# connector_schematic.net
KiCad netlist of a schematic drawn in EAGLE
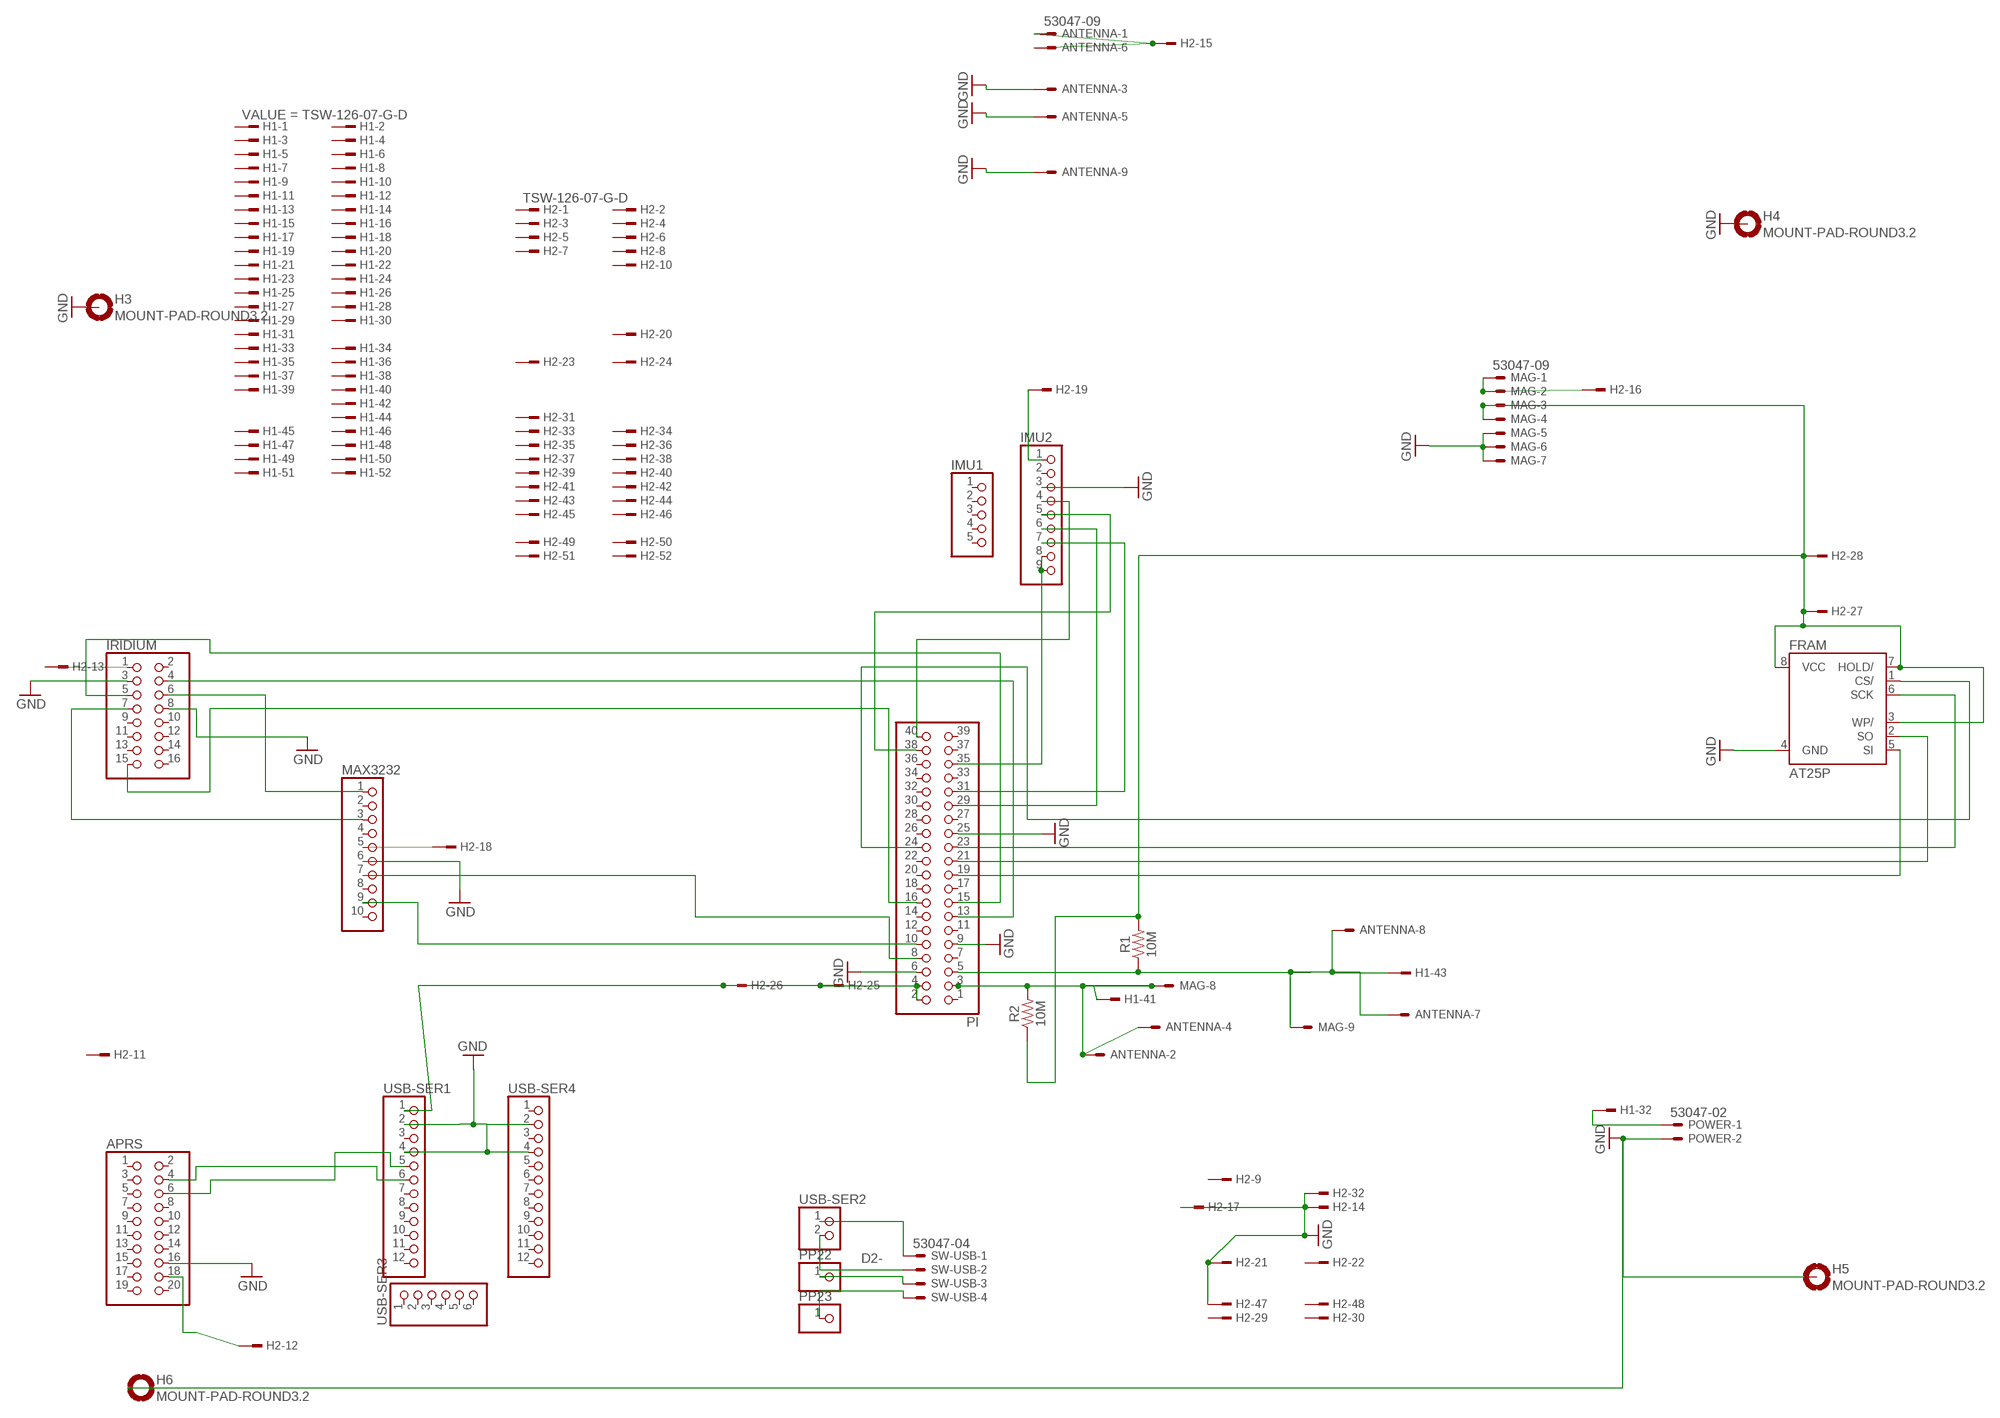
[diagram p0: schematic, sheet 1]

(export (version "E")
  (design (tool "Eeschema 10.0.6"))
  (components
    (comp (ref "ANTENNA")
      (value "53047-09")
      (footprint "eagle-import:53047-09")
      (fields (field (name "MF") "MOLEX") (field (name "MPN") "53047-0910"))
      (libsource (lib "eagle-import") (part "53?-09047"))
    )
    (comp (ref "APRS")
      (value "PINHD-2X10")
      (footprint "eagle-import:2X10")
      (libsource (lib "eagle-import") (part "PINHD-2X10"))
    )
    (comp (ref "FRAM")
      (value "AT25P")
      (footprint "eagle-import:DIL08")
      (fields (field (name "MPN") "CAT25040LI-G"))
      (libsource (lib "eagle-import") (part "AT25P"))
    )
    (comp (ref "H1")
      (value "TSW-126-07-G-D")
      (footprint "eagle-import:TSW-126-XX-G-D")
      (fields (field (name "MF") "Samtec Inc."))
      (libsource (lib "eagle-import") (part "TSW-126--G-D07"))
    )
    (comp (ref "H2")
      (value "TSW-126-07-G-D")
      (footprint "eagle-import:TSW-126-XX-G-D")
      (fields (field (name "MF") "Samtec Inc."))
      (libsource (lib "eagle-import") (part "TSW-126--G-D07"))
    )
    (comp (ref "H3")
      (value "MOUNT-PAD-ROUND3.2")
      (footprint "eagle-import:3,2-PAD")
      (libsource (lib "eagle-import") (part "MOUNT-PAD-ROUND3.2"))
    )
    (comp (ref "H4")
      (value "MOUNT-PAD-ROUND3.2")
      (footprint "eagle-import:3,2-PAD")
      (libsource (lib "eagle-import") (part "MOUNT-PAD-ROUND3.2"))
    )
    (comp (ref "H5")
      (value "MOUNT-PAD-ROUND3.2")
      (footprint "eagle-import:3,2-PAD")
      (libsource (lib "eagle-import") (part "MOUNT-PAD-ROUND3.2"))
    )
    (comp (ref "H6")
      (value "MOUNT-PAD-ROUND3.2")
      (footprint "eagle-import:3,2-PAD")
      (libsource (lib "eagle-import") (part "MOUNT-PAD-ROUND3.2"))
    )
    (comp (ref "IMU1")
      (value "PINHD-1X5")
      (footprint "eagle-import:1X05")
      (libsource (lib "eagle-import") (part "PINHD-1X5"))
    )
    (comp (ref "IMU2")
      (value "PINHD-1X9")
      (footprint "eagle-import:1X09")
      (libsource (lib "eagle-import") (part "PINHD-1X9"))
    )
    (comp (ref "IRIDIUM")
      (value "PINHD-2X8")
      (footprint "eagle-import:2X08")
      (libsource (lib "eagle-import") (part "PINHD-2X8"))
    )
    (comp (ref "MAG")
      (value "53047-09")
      (footprint "eagle-import:53047-09")
      (fields (field (name "MF") "MOLEX") (field (name "MPN") "53047-0910"))
      (libsource (lib "eagle-import") (part "53?-09047"))
    )
    (comp (ref "MAX3232")
      (value "PINHD-1X10")
      (footprint "eagle-import:1X10")
      (libsource (lib "eagle-import") (part "PINHD-1X10"))
    )
    (comp (ref "PI")
      (value "PINHD-2X20")
      (footprint "eagle-import:2X20")
      (libsource (lib "eagle-import") (part "PINHD-2X20"))
    )
    (comp (ref "POWER")
      (value "53047-02")
      (footprint "eagle-import:53047-02")
      (fields (field (name "MF") "MOLEX") (field (name "MPN") "53047-0210"))
      (libsource (lib "eagle-import") (part "53?-02047"))
    )
    (comp (ref "PP22")
      (value "PINHD-1X1")
      (footprint "eagle-import:1X01")
      (libsource (lib "eagle-import") (part "PINHD-1X1"))
    )
    (comp (ref "PP23")
      (value "PINHD-1X1")
      (footprint "eagle-import:1X01")
      (libsource (lib "eagle-import") (part "PINHD-1X1"))
    )
    (comp (ref "R1")
      (value "10M")
      (footprint "eagle-import:AXIAL-0.3")
      (libsource (lib "eagle-import") (part "10MOHM-HORIZ-1/4W-5%"))
    )
    (comp (ref "R2")
      (value "10M")
      (footprint "eagle-import:AXIAL-0.3")
      (libsource (lib "eagle-import") (part "10MOHM-HORIZ-1/4W-5%"))
    )
    (comp (ref "SW-USB")
      (value "53047-04")
      (footprint "eagle-import:53047-04")
      (fields (field (name "MF") "WALDOM/MOLEX") (field (name "MPN") "53047-0410"))
      (libsource (lib "eagle-import") (part "53?-04047"))
    )
    (comp (ref "USB-SER1")
      (value "PINHD-1X12")
      (footprint "eagle-import:1X12")
      (libsource (lib "eagle-import") (part "PINHD-1X12"))
    )
    (comp (ref "USB-SER2")
      (value "PINHD-1X2")
      (footprint "eagle-import:1X02")
      (libsource (lib "eagle-import") (part "PINHD-1X2"))
    )
    (comp (ref "USB-SER3")
      (value "PINHD-1X6")
      (footprint "eagle-import:1X06")
      (libsource (lib "eagle-import") (part "PINHD-1X6"))
    )
    (comp (ref "USB-SER4")
      (value "PINHD-1X12")
      (footprint "eagle-import:1X12")
      (libsource (lib "eagle-import") (part "PINHD-1X12"))
    )
  )
  (nets
    (net (code "1") (name "/D2-") (class "Default")
      (node (ref "SW-USB") (pin "2") (pinfunction "S_2") (pintype "passive"))
      (node (ref "USB-SER2") (pin "2") (pinfunction "2_2") (pintype "passive"))
    )
    (net (code "2") (name "GND") (class "Default")
      (node (ref "ANTENNA") (pin "3") (pinfunction "S_3") (pintype "passive"))
      (node (ref "ANTENNA") (pin "5") (pinfunction "S_5") (pintype "passive"))
      (node (ref "ANTENNA") (pin "9") (pinfunction "S_9") (pintype "passive"))
      (node (ref "APRS") (pin "16") (pinfunction "16_16") (pintype "passive"))
      (node (ref "FRAM") (pin "4") (pinfunction "GND_4") (pintype "power_in"))
      (node (ref "H2") (pin "14") (pinfunction "1_14") (pintype "passive"))
      (node (ref "H2") (pin "17") (pinfunction "1_17") (pintype "passive"))
      (node (ref "H2") (pin "21") (pinfunction "1_21") (pintype "passive"))
      (node (ref "H2") (pin "32") (pinfunction "1_32") (pintype "passive"))
      (node (ref "H2") (pin "47") (pinfunction "1_47") (pintype "passive"))
      (node (ref "H3") (pin "B3,2") (pinfunction "MOUNT_B3,2") (pintype "passive"))
      (node (ref "H4") (pin "B3,2") (pinfunction "MOUNT_B3,2") (pintype "passive"))
      (node (ref "H5") (pin "B3,2") (pinfunction "MOUNT_B3,2") (pintype "passive"))
      (node (ref "H6") (pin "B3,2") (pinfunction "MOUNT_B3,2") (pintype "passive"))
      (node (ref "IMU2") (pin "3") (pinfunction "3_3") (pintype "passive"))
      (node (ref "IRIDIUM") (pin "3") (pinfunction "3_3") (pintype "passive"))
      (node (ref "IRIDIUM") (pin "8") (pinfunction "8_8") (pintype "passive"))
      (node (ref "MAG") (pin "5") (pinfunction "S_5") (pintype "passive"))
      (node (ref "MAG") (pin "6") (pinfunction "S_6") (pintype "passive"))
      (node (ref "MAG") (pin "7") (pinfunction "S_7") (pintype "passive"))
      (node (ref "MAX3232") (pin "6") (pinfunction "6_6") (pintype "passive"))
      (node (ref "PI") (pin "25") (pinfunction "25_25") (pintype "passive"))
      (node (ref "PI") (pin "6") (pinfunction "6_6") (pintype "passive"))
      (node (ref "PI") (pin "9") (pinfunction "9_9") (pintype "passive"))
      (node (ref "POWER") (pin "2") (pinfunction "S_2") (pintype "passive"))
      (node (ref "USB-SER1") (pin "2") (pinfunction "2_2") (pintype "passive"))
      (node (ref "USB-SER1") (pin "4") (pinfunction "4_4") (pintype "passive"))
      (node (ref "USB-SER4") (pin "2") (pinfunction "2_2") (pintype "passive"))
      (node (ref "USB-SER4") (pin "4") (pinfunction "4_4") (pintype "passive"))
    )
    (net (code "3") (name "Net-(ANTENNAA-S)") (class "Default")
      (node (ref "ANTENNA") (pin "1") (pinfunction "S_1") (pintype "passive"))
      (node (ref "ANTENNA") (pin "6") (pinfunction "S_6") (pintype "passive"))
      (node (ref "H2") (pin "15") (pinfunction "1_15") (pintype "passive"))
    )
    (net (code "4") (name "Net-(ANTENNAB-S)") (class "Default")
      (node (ref "ANTENNA") (pin "2") (pinfunction "S_2") (pintype "passive"))
      (node (ref "ANTENNA") (pin "4") (pinfunction "S_4") (pintype "passive"))
      (node (ref "H1") (pin "41") (pinfunction "1_41") (pintype "passive"))
      (node (ref "MAG") (pin "8") (pinfunction "S_8") (pintype "passive"))
      (node (ref "PI") (pin "3") (pinfunction "3_3") (pintype "passive"))
      (node (ref "R2") (pin "P$2") (pinfunction "2_P$2") (pintype "passive"))
    )
    (net (code "5") (name "Net-(ANTENNAG-S)") (class "Default")
      (node (ref "ANTENNA") (pin "7") (pinfunction "S_7") (pintype "passive"))
      (node (ref "ANTENNA") (pin "8") (pinfunction "S_8") (pintype "passive"))
      (node (ref "H1") (pin "43") (pinfunction "1_43") (pintype "passive"))
      (node (ref "MAG") (pin "9") (pinfunction "S_9") (pintype "passive"))
      (node (ref "PI") (pin "5") (pinfunction "5_5") (pintype "passive"))
      (node (ref "R1") (pin "P$1") (pinfunction "1_P$1") (pintype "passive"))
    )
    (net (code "6") (name "Net-(APRS-Pad4)") (class "Default")
      (node (ref "APRS") (pin "4") (pinfunction "4_4") (pintype "passive"))
      (node (ref "USB-SER1") (pin "6") (pinfunction "6_6") (pintype "passive"))
    )
    (net (code "7") (name "Net-(APRS-Pad6)") (class "Default")
      (node (ref "APRS") (pin "6") (pinfunction "6_6") (pintype "passive"))
      (node (ref "USB-SER1") (pin "5") (pinfunction "5_5") (pintype "passive"))
    )
    (net (code "8") (name "Net-(FRAM-CS{slash})") (class "Default")
      (node (ref "FRAM") (pin "1") (pinfunction "CS/_1") (pintype "input"))
      (node (ref "PI") (pin "24") (pinfunction "24_24") (pintype "passive"))
    )
    (net (code "9") (name "Net-(FRAM-HOLD{slash})") (class "Default")
      (node (ref "FRAM") (pin "3") (pinfunction "WP/_3") (pintype "input"))
      (node (ref "FRAM") (pin "7") (pinfunction "HOLD/_7") (pintype "input"))
      (node (ref "FRAM") (pin "8") (pinfunction "VCC_8") (pintype "power_in"))
      (node (ref "H2") (pin "27") (pinfunction "1_27") (pintype "passive"))
      (node (ref "H2") (pin "28") (pinfunction "1_28") (pintype "passive"))
      (node (ref "MAG") (pin "3") (pinfunction "S_3") (pintype "passive"))
      (node (ref "MAG") (pin "4") (pinfunction "S_4") (pintype "passive"))
      (node (ref "R1") (pin "P$2") (pinfunction "2_P$2") (pintype "passive"))
      (node (ref "R2") (pin "P$1") (pinfunction "1_P$1") (pintype "passive"))
    )
    (net (code "10") (name "Net-(FRAM-SCK)") (class "Default")
      (node (ref "FRAM") (pin "6") (pinfunction "SCK_6") (pintype "bidirectional"))
      (node (ref "PI") (pin "23") (pinfunction "23_23") (pintype "passive"))
    )
    (net (code "11") (name "Net-(FRAM-SI)") (class "Default")
      (node (ref "FRAM") (pin "5") (pinfunction "SI_5") (pintype "bidirectional"))
      (node (ref "PI") (pin "19") (pinfunction "19_19") (pintype "passive"))
    )
    (net (code "12") (name "Net-(FRAM-SO)") (class "Default")
      (node (ref "FRAM") (pin "2") (pinfunction "SO_2") (pintype "input"))
      (node (ref "PI") (pin "21") (pinfunction "21_21") (pintype "passive"))
    )
    (net (code "13") (name "Net-(H1Z-1)") (class "Default")
      (node (ref "H1") (pin "32") (pinfunction "1_32") (pintype "passive"))
      (node (ref "POWER") (pin "1") (pinfunction "S_1") (pintype "passive"))
    )
    (net (code "14") (name "Net-(H2D-1)") (class "Default")
      (node (ref "APRS") (pin "18") (pinfunction "18_18") (pintype "passive"))
      (node (ref "H2") (pin "12") (pinfunction "1_12") (pintype "passive"))
    )
    (net (code "15") (name "Net-(H2E-1)") (class "Default")
      (node (ref "H2") (pin "13") (pinfunction "1_13") (pintype "passive"))
      (node (ref "IRIDIUM") (pin "1") (pinfunction "1_1") (pintype "passive"))
    )
    (net (code "16") (name "Net-(H2H-1)") (class "Default")
      (node (ref "H2") (pin "16") (pinfunction "1_16") (pintype "passive"))
      (node (ref "MAG") (pin "1") (pinfunction "S_1") (pintype "passive"))
      (node (ref "MAG") (pin "2") (pinfunction "S_2") (pintype "passive"))
    )
    (net (code "17") (name "Net-(H2J-1)") (class "Default")
      (node (ref "H2") (pin "18") (pinfunction "1_18") (pintype "passive"))
      (node (ref "MAX3232") (pin "5") (pinfunction "5_5") (pintype "passive"))
    )
    (net (code "18") (name "Net-(H2K-1)") (class "Default")
      (node (ref "H2") (pin "19") (pinfunction "1_19") (pintype "passive"))
      (node (ref "IMU2") (pin "1") (pinfunction "1_1") (pintype "passive"))
    )
    (net (code "19") (name "Net-(H2R-1)") (class "Default")
      (node (ref "H2") (pin "25") (pinfunction "1_25") (pintype "passive"))
      (node (ref "H2") (pin "26") (pinfunction "1_26") (pintype "passive"))
      (node (ref "PI") (pin "2") (pinfunction "2_2") (pintype "passive"))
      (node (ref "PI") (pin "4") (pinfunction "4_4") (pintype "passive"))
      (node (ref "USB-SER1") (pin "1") (pinfunction "1_1") (pintype "passive"))
    )
    (net (code "20") (name "Net-(IMU2-Pad4)") (class "Default")
      (node (ref "IMU2") (pin "4") (pinfunction "4_4") (pintype "passive"))
      (node (ref "PI") (pin "40") (pinfunction "40_40") (pintype "passive"))
    )
    (net (code "21") (name "Net-(IMU2-Pad5)") (class "Default")
      (node (ref "IMU2") (pin "5") (pinfunction "5_5") (pintype "passive"))
      (node (ref "PI") (pin "38") (pinfunction "38_38") (pintype "passive"))
    )
    (net (code "22") (name "Net-(IMU2-Pad6)") (class "Default")
      (node (ref "IMU2") (pin "6") (pinfunction "6_6") (pintype "passive"))
      (node (ref "PI") (pin "29") (pinfunction "29_29") (pintype "passive"))
    )
    (net (code "23") (name "Net-(IMU2-Pad7)") (class "Default")
      (node (ref "IMU2") (pin "7") (pinfunction "7_7") (pintype "passive"))
      (node (ref "PI") (pin "31") (pinfunction "31_31") (pintype "passive"))
    )
    (net (code "24") (name "Net-(IMU2-Pad8)") (class "Default")
      (node (ref "IMU2") (pin "8") (pinfunction "8_8") (pintype "passive"))
      (node (ref "IMU2") (pin "9") (pinfunction "9_9") (pintype "passive"))
      (node (ref "PI") (pin "35") (pinfunction "35_35") (pintype "passive"))
    )
    (net (code "25") (name "Net-(IRIDIUM-Pad4)") (class "Default")
      (node (ref "IRIDIUM") (pin "4") (pinfunction "4_4") (pintype "passive"))
      (node (ref "PI") (pin "13") (pinfunction "13_13") (pintype "passive"))
    )
    (net (code "26") (name "Net-(IRIDIUM-Pad5)") (class "Default")
      (node (ref "IRIDIUM") (pin "5") (pinfunction "5_5") (pintype "passive"))
      (node (ref "PI") (pin "15") (pinfunction "15_15") (pintype "passive"))
    )
    (net (code "27") (name "Net-(IRIDIUM-Pad6)") (class "Default")
      (node (ref "IRIDIUM") (pin "6") (pinfunction "6_6") (pintype "passive"))
      (node (ref "MAX3232") (pin "1") (pinfunction "1_1") (pintype "passive"))
    )
    (net (code "28") (name "Net-(IRIDIUM-Pad7)") (class "Default")
      (node (ref "IRIDIUM") (pin "7") (pinfunction "7_7") (pintype "passive"))
      (node (ref "MAX3232") (pin "3") (pinfunction "3_3") (pintype "passive"))
    )
    (net (code "29") (name "Net-(IRIDIUM-Pad15)") (class "Default")
      (node (ref "IRIDIUM") (pin "15") (pinfunction "15_15") (pintype "passive"))
      (node (ref "PI") (pin "16") (pinfunction "16_16") (pintype "passive"))
    )
    (net (code "30") (name "Net-(MAX3232-Pad7)") (class "Default")
      (node (ref "MAX3232") (pin "7") (pinfunction "7_7") (pintype "passive"))
      (node (ref "PI") (pin "8") (pinfunction "8_8") (pintype "passive"))
    )
    (net (code "31") (name "Net-(MAX3232-Pad9)") (class "Default")
      (node (ref "MAX3232") (pin "9") (pinfunction "9_9") (pintype "passive"))
      (node (ref "PI") (pin "10") (pinfunction "10_10") (pintype "passive"))
    )
    (net (code "32") (name "Net-(SW-USBA-S)") (class "Default")
      (node (ref "SW-USB") (pin "1") (pinfunction "S_1") (pintype "passive"))
      (node (ref "USB-SER2") (pin "1") (pinfunction "1_1") (pintype "passive"))
    )
    (net (code "33") (name "Net-(SW-USBC-S)") (class "Default")
      (node (ref "PP22") (pin "1") (pinfunction "1_1") (pintype "passive"))
      (node (ref "SW-USB") (pin "3") (pinfunction "S_3") (pintype "passive"))
    )
    (net (code "34") (name "Net-(SW-USBD-S)") (class "Default")
      (node (ref "PP23") (pin "1") (pinfunction "1_1") (pintype "passive"))
      (node (ref "SW-USB") (pin "4") (pinfunction "S_4") (pintype "passive"))
    )
    (net (code "35") (name "unconnected-(APRS-Pad1)") (class "Default")
      (node (ref "APRS") (pin "1") (pinfunction "1_1") (pintype "passive"))
    )
    (net (code "36") (name "unconnected-(APRS-Pad2)") (class "Default")
      (node (ref "APRS") (pin "2") (pinfunction "2_2") (pintype "passive"))
    )
    (net (code "37") (name "unconnected-(APRS-Pad3)") (class "Default")
      (node (ref "APRS") (pin "3") (pinfunction "3_3") (pintype "passive"))
    )
    (net (code "38") (name "unconnected-(APRS-Pad5)") (class "Default")
      (node (ref "APRS") (pin "5") (pinfunction "5_5") (pintype "passive"))
    )
    (net (code "39") (name "unconnected-(APRS-Pad7)") (class "Default")
      (node (ref "APRS") (pin "7") (pinfunction "7_7") (pintype "passive"))
    )
    (net (code "40") (name "unconnected-(APRS-Pad8)") (class "Default")
      (node (ref "APRS") (pin "8") (pinfunction "8_8") (pintype "passive"))
    )
    (net (code "41") (name "unconnected-(APRS-Pad9)") (class "Default")
      (node (ref "APRS") (pin "9") (pinfunction "9_9") (pintype "passive"))
    )
    (net (code "42") (name "unconnected-(APRS-Pad10)") (class "Default")
      (node (ref "APRS") (pin "10") (pinfunction "10_10") (pintype "passive"))
    )
    (net (code "43") (name "unconnected-(APRS-Pad11)") (class "Default")
      (node (ref "APRS") (pin "11") (pinfunction "11_11") (pintype "passive"))
    )
    (net (code "44") (name "unconnected-(APRS-Pad12)") (class "Default")
      (node (ref "APRS") (pin "12") (pinfunction "12_12") (pintype "passive"))
    )
    (net (code "45") (name "unconnected-(APRS-Pad13)") (class "Default")
      (node (ref "APRS") (pin "13") (pinfunction "13_13") (pintype "passive"))
    )
    (net (code "46") (name "unconnected-(APRS-Pad14)") (class "Default")
      (node (ref "APRS") (pin "14") (pinfunction "14_14") (pintype "passive"))
    )
    (net (code "47") (name "unconnected-(APRS-Pad15)") (class "Default")
      (node (ref "APRS") (pin "15") (pinfunction "15_15") (pintype "passive"))
    )
    (net (code "48") (name "unconnected-(APRS-Pad17)") (class "Default")
      (node (ref "APRS") (pin "17") (pinfunction "17_17") (pintype "passive"))
    )
    (net (code "49") (name "unconnected-(APRS-Pad19)") (class "Default")
      (node (ref "APRS") (pin "19") (pinfunction "19_19") (pintype "passive"))
    )
    (net (code "50") (name "unconnected-(APRS-Pad20)") (class "Default")
      (node (ref "APRS") (pin "20") (pinfunction "20_20") (pintype "passive"))
    )
    (net (code "51") (name "unconnected-(H1-Pad1)") (class "Default")
      (node (ref "H1") (pin "1") (pinfunction "1_1") (pintype "passive"))
    )
    (net (code "52") (name "unconnected-(H1AA-1-Pad33)") (class "Default")
      (node (ref "H1") (pin "33") (pinfunction "1_33") (pintype "passive"))
    )
    (net (code "53") (name "unconnected-(H1AB-1-Pad34)") (class "Default")
      (node (ref "H1") (pin "34") (pinfunction "1_34") (pintype "passive"))
    )
    (net (code "54") (name "unconnected-(H1AC-1-Pad35)") (class "Default")
      (node (ref "H1") (pin "35") (pinfunction "1_35") (pintype "passive"))
    )
    (net (code "55") (name "unconnected-(H1AD-1-Pad36)") (class "Default")
      (node (ref "H1") (pin "36") (pinfunction "1_36") (pintype "passive"))
    )
    (net (code "56") (name "unconnected-(H1AE-1-Pad37)") (class "Default")
      (node (ref "H1") (pin "37") (pinfunction "1_37") (pintype "passive"))
    )
    (net (code "57") (name "unconnected-(H1AF-1-Pad38)") (class "Default")
      (node (ref "H1") (pin "38") (pinfunction "1_38") (pintype "passive"))
    )
    (net (code "58") (name "unconnected-(H1AG-1-Pad39)") (class "Default")
      (node (ref "H1") (pin "39") (pinfunction "1_39") (pintype "passive"))
    )
    (net (code "59") (name "unconnected-(H1AH-1-Pad4)") (class "Default")
      (node (ref "H1") (pin "4") (pinfunction "1_4") (pintype "passive"))
    )
    (net (code "60") (name "unconnected-(H1AI-1-Pad40)") (class "Default")
      (node (ref "H1") (pin "40") (pinfunction "1_40") (pintype "passive"))
    )
    (net (code "61") (name "unconnected-(H1AK-1-Pad42)") (class "Default")
      (node (ref "H1") (pin "42") (pinfunction "1_42") (pintype "passive"))
    )
    (net (code "62") (name "unconnected-(H1AM-1-Pad44)") (class "Default")
      (node (ref "H1") (pin "44") (pinfunction "1_44") (pintype "passive"))
    )
    (net (code "63") (name "unconnected-(H1AN-1-Pad45)") (class "Default")
      (node (ref "H1") (pin "45") (pinfunction "1_45") (pintype "passive"))
    )
    (net (code "64") (name "unconnected-(H1AO-1-Pad46)") (class "Default")
      (node (ref "H1") (pin "46") (pinfunction "1_46") (pintype "passive"))
    )
    (net (code "65") (name "unconnected-(H1AP-1-Pad47)") (class "Default")
      (node (ref "H1") (pin "47") (pinfunction "1_47") (pintype "passive"))
    )
    (net (code "66") (name "unconnected-(H1AQ-1-Pad48)") (class "Default")
      (node (ref "H1") (pin "48") (pinfunction "1_48") (pintype "passive"))
    )
    (net (code "67") (name "unconnected-(H1AR-1-Pad49)") (class "Default")
      (node (ref "H1") (pin "49") (pinfunction "1_49") (pintype "passive"))
    )
    (net (code "68") (name "unconnected-(H1AS-1-Pad5)") (class "Default")
      (node (ref "H1") (pin "5") (pinfunction "1_5") (pintype "passive"))
    )
    (net (code "69") (name "unconnected-(H1AT-1-Pad50)") (class "Default")
      (node (ref "H1") (pin "50") (pinfunction "1_50") (pintype "passive"))
    )
    (net (code "70") (name "unconnected-(H1AU-1-Pad51)") (class "Default")
      (node (ref "H1") (pin "51") (pinfunction "1_51") (pintype "passive"))
    )
    (net (code "71") (name "unconnected-(H1AV-1-Pad52)") (class "Default")
      (node (ref "H1") (pin "52") (pinfunction "1_52") (pintype "passive"))
    )
    (net (code "72") (name "unconnected-(H1AW-1-Pad6)") (class "Default")
      (node (ref "H1") (pin "6") (pinfunction "1_6") (pintype "passive"))
    )
    (net (code "73") (name "unconnected-(H1AX-1-Pad7)") (class "Default")
      (node (ref "H1") (pin "7") (pinfunction "1_7") (pintype "passive"))
    )
    (net (code "74") (name "unconnected-(H1AY-1-Pad8)") (class "Default")
      (node (ref "H1") (pin "8") (pinfunction "1_8") (pintype "passive"))
    )
    (net (code "75") (name "unconnected-(H1AZ-1-Pad9)") (class "Default")
      (node (ref "H1") (pin "9") (pinfunction "1_9") (pintype "passive"))
    )
    (net (code "76") (name "unconnected-(H1B-1-Pad10)") (class "Default")
      (node (ref "H1") (pin "10") (pinfunction "1_10") (pintype "passive"))
    )
    (net (code "77") (name "unconnected-(H1C-1-Pad11)") (class "Default")
      (node (ref "H1") (pin "11") (pinfunction "1_11") (pintype "passive"))
    )
    (net (code "78") (name "unconnected-(H1D-1-Pad12)") (class "Default")
      (node (ref "H1") (pin "12") (pinfunction "1_12") (pintype "passive"))
    )
    (net (code "79") (name "unconnected-(H1E-1-Pad13)") (class "Default")
      (node (ref "H1") (pin "13") (pinfunction "1_13") (pintype "passive"))
    )
    (net (code "80") (name "unconnected-(H1F-1-Pad14)") (class "Default")
      (node (ref "H1") (pin "14") (pinfunction "1_14") (pintype "passive"))
    )
    (net (code "81") (name "unconnected-(H1G-1-Pad15)") (class "Default")
      (node (ref "H1") (pin "15") (pinfunction "1_15") (pintype "passive"))
    )
    (net (code "82") (name "unconnected-(H1H-1-Pad16)") (class "Default")
      (node (ref "H1") (pin "16") (pinfunction "1_16") (pintype "passive"))
    )
    (net (code "83") (name "unconnected-(H1I-1-Pad17)") (class "Default")
      (node (ref "H1") (pin "17") (pinfunction "1_17") (pintype "passive"))
    )
    (net (code "84") (name "unconnected-(H1J-1-Pad18)") (class "Default")
      (node (ref "H1") (pin "18") (pinfunction "1_18") (pintype "passive"))
    )
    (net (code "85") (name "unconnected-(H1K-1-Pad19)") (class "Default")
      (node (ref "H1") (pin "19") (pinfunction "1_19") (pintype "passive"))
    )
    (net (code "86") (name "unconnected-(H1L-1-Pad2)") (class "Default")
      (node (ref "H1") (pin "2") (pinfunction "1_2") (pintype "passive"))
    )
    (net (code "87") (name "unconnected-(H1M-1-Pad20)") (class "Default")
      (node (ref "H1") (pin "20") (pinfunction "1_20") (pintype "passive"))
    )
    (net (code "88") (name "unconnected-(H1N-1-Pad21)") (class "Default")
      (node (ref "H1") (pin "21") (pinfunction "1_21") (pintype "passive"))
    )
    (net (code "89") (name "unconnected-(H1O-1-Pad22)") (class "Default")
      (node (ref "H1") (pin "22") (pinfunction "1_22") (pintype "passive"))
    )
    (net (code "90") (name "unconnected-(H1P-1-Pad23)") (class "Default")
      (node (ref "H1") (pin "23") (pinfunction "1_23") (pintype "passive"))
    )
    (net (code "91") (name "unconnected-(H1Q-1-Pad24)") (class "Default")
      (node (ref "H1") (pin "24") (pinfunction "1_24") (pintype "passive"))
    )
    (net (code "92") (name "unconnected-(H1R-1-Pad25)") (class "Default")
      (node (ref "H1") (pin "25") (pinfunction "1_25") (pintype "passive"))
    )
    (net (code "93") (name "unconnected-(H1S-1-Pad26)") (class "Default")
      (node (ref "H1") (pin "26") (pinfunction "1_26") (pintype "passive"))
    )
    (net (code "94") (name "unconnected-(H1T-1-Pad27)") (class "Default")
      (node (ref "H1") (pin "27") (pinfunction "1_27") (pintype "passive"))
    )
    (net (code "95") (name "unconnected-(H1U-1-Pad28)") (class "Default")
      (node (ref "H1") (pin "28") (pinfunction "1_28") (pintype "passive"))
    )
    (net (code "96") (name "unconnected-(H1V-1-Pad29)") (class "Default")
      (node (ref "H1") (pin "29") (pinfunction "1_29") (pintype "passive"))
    )
    (net (code "97") (name "unconnected-(H1W-1-Pad3)") (class "Default")
      (node (ref "H1") (pin "3") (pinfunction "1_3") (pintype "passive"))
    )
    (net (code "98") (name "unconnected-(H1X-1-Pad30)") (class "Default")
      (node (ref "H1") (pin "30") (pinfunction "1_30") (pintype "passive"))
    )
    (net (code "99") (name "unconnected-(H1Y-1-Pad31)") (class "Default")
      (node (ref "H1") (pin "31") (pinfunction "1_31") (pintype "passive"))
    )
    (net (code "100") (name "unconnected-(H2-Pad1)") (class "Default")
      (node (ref "H2") (pin "1") (pinfunction "1_1") (pintype "passive"))
    )
    (net (code "101") (name "unconnected-(H2AA-1-Pad33)") (class "Default")
      (node (ref "H2") (pin "33") (pinfunction "1_33") (pintype "passive"))
    )
    (net (code "102") (name "unconnected-(H2AB-1-Pad34)") (class "Default")
      (node (ref "H2") (pin "34") (pinfunction "1_34") (pintype "passive"))
    )
    (net (code "103") (name "unconnected-(H2AC-1-Pad35)") (class "Default")
      (node (ref "H2") (pin "35") (pinfunction "1_35") (pintype "passive"))
    )
    (net (code "104") (name "unconnected-(H2AD-1-Pad36)") (class "Default")
      (node (ref "H2") (pin "36") (pinfunction "1_36") (pintype "passive"))
    )
    (net (code "105") (name "unconnected-(H2AE-1-Pad37)") (class "Default")
      (node (ref "H2") (pin "37") (pinfunction "1_37") (pintype "passive"))
    )
    (net (code "106") (name "unconnected-(H2AF-1-Pad38)") (class "Default")
      (node (ref "H2") (pin "38") (pinfunction "1_38") (pintype "passive"))
    )
    (net (code "107") (name "unconnected-(H2AG-1-Pad39)") (class "Default")
      (node (ref "H2") (pin "39") (pinfunction "1_39") (pintype "passive"))
    )
    (net (code "108") (name "unconnected-(H2AH-1-Pad4)") (class "Default")
      (node (ref "H2") (pin "4") (pinfunction "1_4") (pintype "passive"))
    )
    (net (code "109") (name "unconnected-(H2AI-1-Pad40)") (class "Default")
      (node (ref "H2") (pin "40") (pinfunction "1_40") (pintype "passive"))
    )
    (net (code "110") (name "unconnected-(H2AJ-1-Pad41)") (class "Default")
      (node (ref "H2") (pin "41") (pinfunction "1_41") (pintype "passive"))
    )
    (net (code "111") (name "unconnected-(H2AK-1-Pad42)") (class "Default")
      (node (ref "H2") (pin "42") (pinfunction "1_42") (pintype "passive"))
    )
    (net (code "112") (name "unconnected-(H2AL-1-Pad43)") (class "Default")
      (node (ref "H2") (pin "43") (pinfunction "1_43") (pintype "passive"))
    )
    (net (code "113") (name "unconnected-(H2AM-1-Pad44)") (class "Default")
      (node (ref "H2") (pin "44") (pinfunction "1_44") (pintype "passive"))
    )
    (net (code "114") (name "unconnected-(H2AN-1-Pad45)") (class "Default")
      (node (ref "H2") (pin "45") (pinfunction "1_45") (pintype "passive"))
    )
    (net (code "115") (name "unconnected-(H2AO-1-Pad46)") (class "Default")
      (node (ref "H2") (pin "46") (pinfunction "1_46") (pintype "passive"))
    )
    (net (code "116") (name "unconnected-(H2AQ-1-Pad48)") (class "Default")
      (node (ref "H2") (pin "48") (pinfunction "1_48") (pintype "passive"))
    )
    (net (code "117") (name "unconnected-(H2AR-1-Pad49)") (class "Default")
      (node (ref "H2") (pin "49") (pinfunction "1_49") (pintype "passive"))
    )
    (net (code "118") (name "unconnected-(H2AS-1-Pad5)") (class "Default")
      (node (ref "H2") (pin "5") (pinfunction "1_5") (pintype "passive"))
    )
    (net (code "119") (name "unconnected-(H2AT-1-Pad50)") (class "Default")
      (node (ref "H2") (pin "50") (pinfunction "1_50") (pintype "passive"))
    )
    (net (code "120") (name "unconnected-(H2AU-1-Pad51)") (class "Default")
      (node (ref "H2") (pin "51") (pinfunction "1_51") (pintype "passive"))
    )
    (net (code "121") (name "unconnected-(H2AV-1-Pad52)") (class "Default")
      (node (ref "H2") (pin "52") (pinfunction "1_52") (pintype "passive"))
    )
    (net (code "122") (name "unconnected-(H2AW-1-Pad6)") (class "Default")
      (node (ref "H2") (pin "6") (pinfunction "1_6") (pintype "passive"))
    )
    (net (code "123") (name "unconnected-(H2AX-1-Pad7)") (class "Default")
      (node (ref "H2") (pin "7") (pinfunction "1_7") (pintype "passive"))
    )
    (net (code "124") (name "unconnected-(H2AY-1-Pad8)") (class "Default")
      (node (ref "H2") (pin "8") (pinfunction "1_8") (pintype "passive"))
    )
    (net (code "125") (name "unconnected-(H2AZ-1-Pad9)") (class "Default")
      (node (ref "H2") (pin "9") (pinfunction "1_9") (pintype "passive"))
    )
    (net (code "126") (name "unconnected-(H2B-1-Pad10)") (class "Default")
      (node (ref "H2") (pin "10") (pinfunction "1_10") (pintype "passive"))
    )
    (net (code "127") (name "unconnected-(H2C-1-Pad11)") (class "Default")
      (node (ref "H2") (pin "11") (pinfunction "1_11") (pintype "passive"))
    )
    (net (code "128") (name "unconnected-(H2L-1-Pad2)") (class "Default")
      (node (ref "H2") (pin "2") (pinfunction "1_2") (pintype "passive"))
    )
    (net (code "129") (name "unconnected-(H2M-1-Pad20)") (class "Default")
      (node (ref "H2") (pin "20") (pinfunction "1_20") (pintype "passive"))
    )
    (net (code "130") (name "unconnected-(H2O-1-Pad22)") (class "Default")
      (node (ref "H2") (pin "22") (pinfunction "1_22") (pintype "passive"))
    )
    (net (code "131") (name "unconnected-(H2P-1-Pad23)") (class "Default")
      (node (ref "H2") (pin "23") (pinfunction "1_23") (pintype "passive"))
    )
    (net (code "132") (name "unconnected-(H2Q-1-Pad24)") (class "Default")
      (node (ref "H2") (pin "24") (pinfunction "1_24") (pintype "passive"))
    )
    (net (code "133") (name "unconnected-(H2V-1-Pad29)") (class "Default")
      (node (ref "H2") (pin "29") (pinfunction "1_29") (pintype "passive"))
    )
    (net (code "134") (name "unconnected-(H2W-1-Pad3)") (class "Default")
      (node (ref "H2") (pin "3") (pinfunction "1_3") (pintype "passive"))
    )
    (net (code "135") (name "unconnected-(H2X-1-Pad30)") (class "Default")
      (node (ref "H2") (pin "30") (pinfunction "1_30") (pintype "passive"))
    )
    (net (code "136") (name "unconnected-(H2Y-1-Pad31)") (class "Default")
      (node (ref "H2") (pin "31") (pinfunction "1_31") (pintype "passive"))
    )
    (net (code "137") (name "unconnected-(IMU1-Pad1)") (class "Default")
      (node (ref "IMU1") (pin "1") (pinfunction "1_1") (pintype "passive"))
    )
    (net (code "138") (name "unconnected-(IMU1-Pad2)") (class "Default")
      (node (ref "IMU1") (pin "2") (pinfunction "2_2") (pintype "passive"))
    )
    (net (code "139") (name "unconnected-(IMU1-Pad3)") (class "Default")
      (node (ref "IMU1") (pin "3") (pinfunction "3_3") (pintype "passive"))
    )
    (net (code "140") (name "unconnected-(IMU1-Pad4)") (class "Default")
      (node (ref "IMU1") (pin "4") (pinfunction "4_4") (pintype "passive"))
    )
    (net (code "141") (name "unconnected-(IMU1-Pad5)") (class "Default")
      (node (ref "IMU1") (pin "5") (pinfunction "5_5") (pintype "passive"))
    )
    (net (code "142") (name "unconnected-(IMU2-Pad2)") (class "Default")
      (node (ref "IMU2") (pin "2") (pinfunction "2_2") (pintype "passive"))
    )
    (net (code "143") (name "unconnected-(IRIDIUM-Pad2)") (class "Default")
      (node (ref "IRIDIUM") (pin "2") (pinfunction "2_2") (pintype "passive"))
    )
    (net (code "144") (name "unconnected-(IRIDIUM-Pad9)") (class "Default")
      (node (ref "IRIDIUM") (pin "9") (pinfunction "9_9") (pintype "passive"))
    )
    (net (code "145") (name "unconnected-(IRIDIUM-Pad10)") (class "Default")
      (node (ref "IRIDIUM") (pin "10") (pinfunction "10_10") (pintype "passive"))
    )
    (net (code "146") (name "unconnected-(IRIDIUM-Pad11)") (class "Default")
      (node (ref "IRIDIUM") (pin "11") (pinfunction "11_11") (pintype "passive"))
    )
    (net (code "147") (name "unconnected-(IRIDIUM-Pad12)") (class "Default")
      (node (ref "IRIDIUM") (pin "12") (pinfunction "12_12") (pintype "passive"))
    )
    (net (code "148") (name "unconnected-(IRIDIUM-Pad13)") (class "Default")
      (node (ref "IRIDIUM") (pin "13") (pinfunction "13_13") (pintype "passive"))
    )
    (net (code "149") (name "unconnected-(IRIDIUM-Pad14)") (class "Default")
      (node (ref "IRIDIUM") (pin "14") (pinfunction "14_14") (pintype "passive"))
    )
    (net (code "150") (name "unconnected-(IRIDIUM-Pad16)") (class "Default")
      (node (ref "IRIDIUM") (pin "16") (pinfunction "16_16") (pintype "passive"))
    )
    (net (code "151") (name "unconnected-(MAX3232-Pad2)") (class "Default")
      (node (ref "MAX3232") (pin "2") (pinfunction "2_2") (pintype "passive"))
    )
    (net (code "152") (name "unconnected-(MAX3232-Pad4)") (class "Default")
      (node (ref "MAX3232") (pin "4") (pinfunction "4_4") (pintype "passive"))
    )
    (net (code "153") (name "unconnected-(MAX3232-Pad8)") (class "Default")
      (node (ref "MAX3232") (pin "8") (pinfunction "8_8") (pintype "passive"))
    )
    (net (code "154") (name "unconnected-(MAX3232-Pad10)") (class "Default")
      (node (ref "MAX3232") (pin "10") (pinfunction "10_10") (pintype "passive"))
    )
    (net (code "155") (name "unconnected-(PI-Pad1)") (class "Default")
      (node (ref "PI") (pin "1") (pinfunction "1_1") (pintype "passive"))
    )
    (net (code "156") (name "unconnected-(PI-Pad7)") (class "Default")
      (node (ref "PI") (pin "7") (pinfunction "7_7") (pintype "passive"))
    )
    (net (code "157") (name "unconnected-(PI-Pad11)") (class "Default")
      (node (ref "PI") (pin "11") (pinfunction "11_11") (pintype "passive"))
    )
    (net (code "158") (name "unconnected-(PI-Pad12)") (class "Default")
      (node (ref "PI") (pin "12") (pinfunction "12_12") (pintype "passive"))
    )
    (net (code "159") (name "unconnected-(PI-Pad14)") (class "Default")
      (node (ref "PI") (pin "14") (pinfunction "14_14") (pintype "passive"))
    )
    (net (code "160") (name "unconnected-(PI-Pad17)") (class "Default")
      (node (ref "PI") (pin "17") (pinfunction "17_17") (pintype "passive"))
    )
    (net (code "161") (name "unconnected-(PI-Pad18)") (class "Default")
      (node (ref "PI") (pin "18") (pinfunction "18_18") (pintype "passive"))
    )
    (net (code "162") (name "unconnected-(PI-Pad20)") (class "Default")
      (node (ref "PI") (pin "20") (pinfunction "20_20") (pintype "passive"))
    )
    (net (code "163") (name "unconnected-(PI-Pad22)") (class "Default")
      (node (ref "PI") (pin "22") (pinfunction "22_22") (pintype "passive"))
    )
    (net (code "164") (name "unconnected-(PI-Pad26)") (class "Default")
      (node (ref "PI") (pin "26") (pinfunction "26_26") (pintype "passive"))
    )
    (net (code "165") (name "unconnected-(PI-Pad27)") (class "Default")
      (node (ref "PI") (pin "27") (pinfunction "27_27") (pintype "passive"))
    )
    (net (code "166") (name "unconnected-(PI-Pad28)") (class "Default")
      (node (ref "PI") (pin "28") (pinfunction "28_28") (pintype "passive"))
    )
    (net (code "167") (name "unconnected-(PI-Pad30)") (class "Default")
      (node (ref "PI") (pin "30") (pinfunction "30_30") (pintype "passive"))
    )
    (net (code "168") (name "unconnected-(PI-Pad32)") (class "Default")
      (node (ref "PI") (pin "32") (pinfunction "32_32") (pintype "passive"))
    )
    (net (code "169") (name "unconnected-(PI-Pad33)") (class "Default")
      (node (ref "PI") (pin "33") (pinfunction "33_33") (pintype "passive"))
    )
    (net (code "170") (name "unconnected-(PI-Pad34)") (class "Default")
      (node (ref "PI") (pin "34") (pinfunction "34_34") (pintype "passive"))
    )
    (net (code "171") (name "unconnected-(PI-Pad36)") (class "Default")
      (node (ref "PI") (pin "36") (pinfunction "36_36") (pintype "passive"))
    )
    (net (code "172") (name "unconnected-(PI-Pad37)") (class "Default")
      (node (ref "PI") (pin "37") (pinfunction "37_37") (pintype "passive"))
    )
    (net (code "173") (name "unconnected-(PI-Pad39)") (class "Default")
      (node (ref "PI") (pin "39") (pinfunction "39_39") (pintype "passive"))
    )
    (net (code "174") (name "unconnected-(USB-SER1-Pad3)") (class "Default")
      (node (ref "USB-SER1") (pin "3") (pinfunction "3_3") (pintype "passive"))
    )
    (net (code "175") (name "unconnected-(USB-SER1-Pad7)") (class "Default")
      (node (ref "USB-SER1") (pin "7") (pinfunction "7_7") (pintype "passive"))
    )
    (net (code "176") (name "unconnected-(USB-SER1-Pad8)") (class "Default")
      (node (ref "USB-SER1") (pin "8") (pinfunction "8_8") (pintype "passive"))
    )
    (net (code "177") (name "unconnected-(USB-SER1-Pad9)") (class "Default")
      (node (ref "USB-SER1") (pin "9") (pinfunction "9_9") (pintype "passive"))
    )
    (net (code "178") (name "unconnected-(USB-SER1-Pad10)") (class "Default")
      (node (ref "USB-SER1") (pin "10") (pinfunction "10_10") (pintype "passive"))
    )
    (net (code "179") (name "unconnected-(USB-SER1-Pad11)") (class "Default")
      (node (ref "USB-SER1") (pin "11") (pinfunction "11_11") (pintype "passive"))
    )
    (net (code "180") (name "unconnected-(USB-SER1-Pad12)") (class "Default")
      (node (ref "USB-SER1") (pin "12") (pinfunction "12_12") (pintype "passive"))
    )
    (net (code "181") (name "unconnected-(USB-SER3-Pad1)") (class "Default")
      (node (ref "USB-SER3") (pin "1") (pinfunction "1_1") (pintype "passive"))
    )
    (net (code "182") (name "unconnected-(USB-SER3-Pad2)") (class "Default")
      (node (ref "USB-SER3") (pin "2") (pinfunction "2_2") (pintype "passive"))
    )
    (net (code "183") (name "unconnected-(USB-SER3-Pad3)") (class "Default")
      (node (ref "USB-SER3") (pin "3") (pinfunction "3_3") (pintype "passive"))
    )
    (net (code "184") (name "unconnected-(USB-SER3-Pad4)") (class "Default")
      (node (ref "USB-SER3") (pin "4") (pinfunction "4_4") (pintype "passive"))
    )
    (net (code "185") (name "unconnected-(USB-SER3-Pad5)") (class "Default")
      (node (ref "USB-SER3") (pin "5") (pinfunction "5_5") (pintype "passive"))
    )
    (net (code "186") (name "unconnected-(USB-SER3-Pad6)") (class "Default")
      (node (ref "USB-SER3") (pin "6") (pinfunction "6_6") (pintype "passive"))
    )
    (net (code "187") (name "unconnected-(USB-SER4-Pad1)") (class "Default")
      (node (ref "USB-SER4") (pin "1") (pinfunction "1_1") (pintype "passive"))
    )
    (net (code "188") (name "unconnected-(USB-SER4-Pad3)") (class "Default")
      (node (ref "USB-SER4") (pin "3") (pinfunction "3_3") (pintype "passive"))
    )
    (net (code "189") (name "unconnected-(USB-SER4-Pad5)") (class "Default")
      (node (ref "USB-SER4") (pin "5") (pinfunction "5_5") (pintype "passive"))
    )
    (net (code "190") (name "unconnected-(USB-SER4-Pad6)") (class "Default")
      (node (ref "USB-SER4") (pin "6") (pinfunction "6_6") (pintype "passive"))
    )
    (net (code "191") (name "unconnected-(USB-SER4-Pad7)") (class "Default")
      (node (ref "USB-SER4") (pin "7") (pinfunction "7_7") (pintype "passive"))
    )
    (net (code "192") (name "unconnected-(USB-SER4-Pad8)") (class "Default")
      (node (ref "USB-SER4") (pin "8") (pinfunction "8_8") (pintype "passive"))
    )
    (net (code "193") (name "unconnected-(USB-SER4-Pad9)") (class "Default")
      (node (ref "USB-SER4") (pin "9") (pinfunction "9_9") (pintype "passive"))
    )
    (net (code "194") (name "unconnected-(USB-SER4-Pad10)") (class "Default")
      (node (ref "USB-SER4") (pin "10") (pinfunction "10_10") (pintype "passive"))
    )
    (net (code "195") (name "unconnected-(USB-SER4-Pad11)") (class "Default")
      (node (ref "USB-SER4") (pin "11") (pinfunction "11_11") (pintype "passive"))
    )
    (net (code "196") (name "unconnected-(USB-SER4-Pad12)") (class "Default")
      (node (ref "USB-SER4") (pin "12") (pinfunction "12_12") (pintype "passive"))
    )
  )
)
